# Supply_Driver_12V.net
KiCad netlist of a schematic drawn in Altium Designer
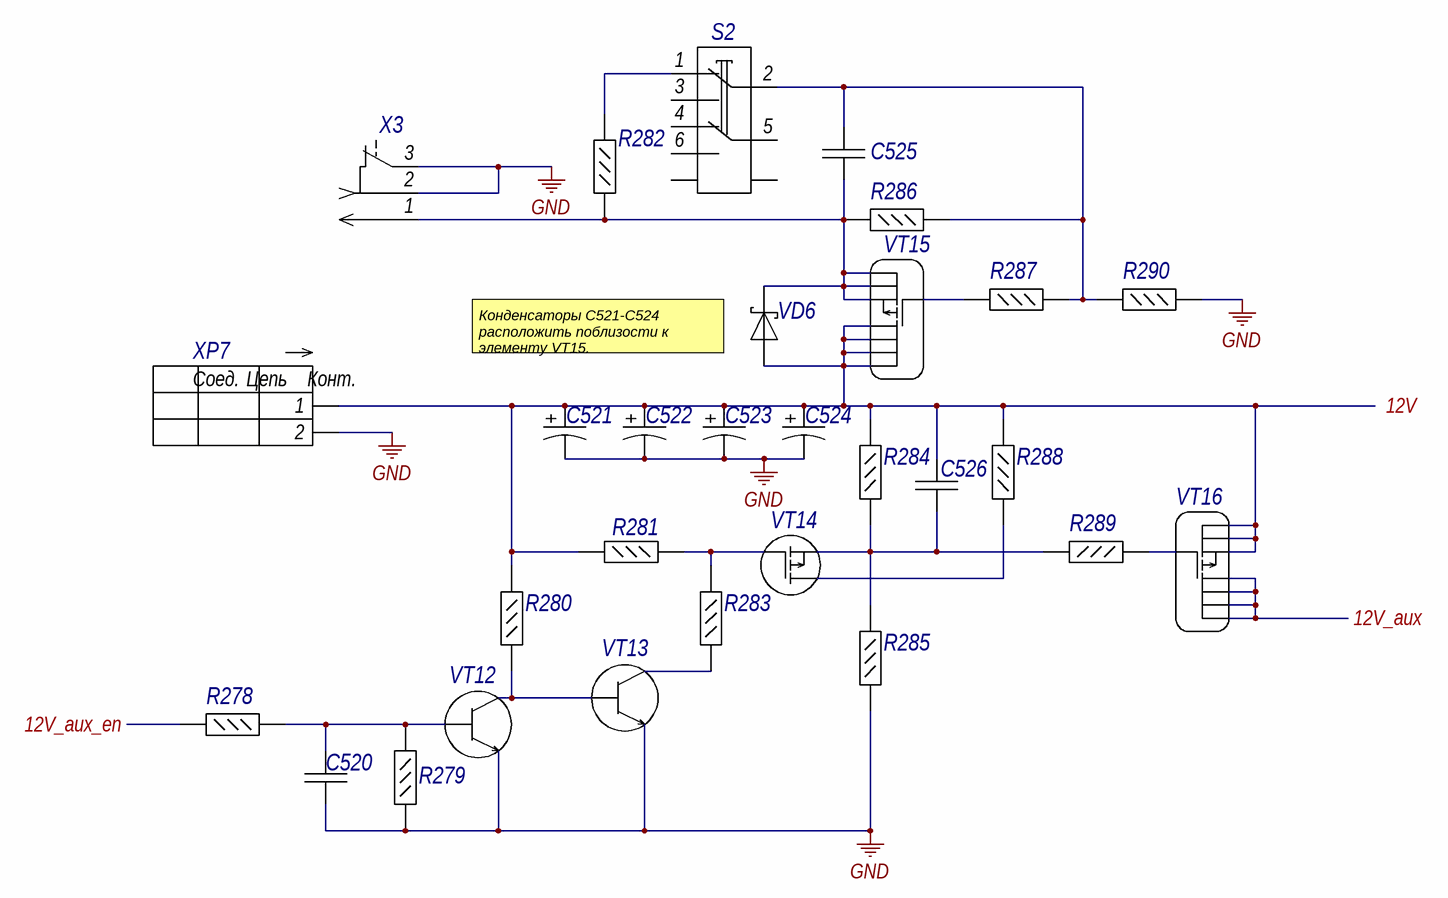
[diagram p0: Supply Driver 12V.SchDoc]

(export (version "E")
  (design (tool "Eeschema 10.0.6"))
  (components
    (comp (ref "C520")
      (value "C1005X7R1E104M")
      (footprint "CAPC1005X55X10LL05")
      (description "Chip Capacitor, 0.1 uF, +/- 20%, 25 V, -55 to 125 degC, 0402 (1005 Metric), RoHS, Tape and Reel")
      (fields (field (name "TOLERANCE") "20%"))
      (libsource (lib "MiniPC DB") (part "CAP_NP"))
    )
    (comp (ref "C521")
      (value "EEH-ZA1E331P")
      (footprint "PNSC-EEH-ZA1E331P_M")
      (fields (field (name "TOLERANCE") "20%"))
      (libsource (lib "MiniPC DB") (part "CAP_P"))
    )
    (comp (ref "C522")
      (value "EEH-ZA1E331P")
      (footprint "PNSC-EEH-ZA1E331P_M")
      (fields (field (name "TOLERANCE") "20%"))
      (libsource (lib "MiniPC DB") (part "CAP_P"))
    )
    (comp (ref "C523")
      (value "EEH-ZA1E331P")
      (footprint "PNSC-EEH-ZA1E331P_M")
      (fields (field (name "TOLERANCE") "20%"))
      (libsource (lib "MiniPC DB") (part "CAP_P"))
    )
    (comp (ref "C524")
      (value "EEH-ZA1E331P")
      (footprint "PNSC-EEH-ZA1E331P_M")
      (fields (field (name "TOLERANCE") "20%"))
      (libsource (lib "MiniPC DB") (part "CAP_P"))
    )
    (comp (ref "C525")
      (value "CGB2A1X5R1E105K033BC")
      (footprint "CAPC1005X33X10LL5")
      (description "Chip Capacitor, 1 uF, +/- 10%, 25 V, -55 to 85 degC, 0402 (1005 Metric), RoHS, Tape and Reel")
      (fields (field (name "TOLERANCE") "10%"))
      (libsource (lib "MiniPC DB") (part "CAP_NP"))
    )
    (comp (ref "C526")
      (value "CGB2A1X5R1E105K033BC")
      (footprint "CAPC1005X33X10LL5")
      (description "Chip Capacitor, 1 uF, +/- 10%, 25 V, -55 to 85 degC, 0402 (1005 Metric), RoHS, Tape and Reel")
      (fields (field (name "TOLERANCE") "10%"))
      (libsource (lib "MiniPC DB") (part "CAP_NP"))
    )
    (comp (ref "R278")
      (value "ERJ-2RKF1001X")
      (footprint "RESC1005X40X25LL05T05")
      (description "Chip Resistor, 1 KOhm, +/- 1%, 100 mW, -55 to 155 degC, 0402 (1005 Metric), RoHS, Tape and Reel")
      (fields (field (name "TOLERANCE") "1%") (field (name "MANUFACTURER") "Basic Passives"))
      (libsource (lib "") (part "RES-0.05_2"))
    )
    (comp (ref "R279")
      (value "ERJ-2RKF1002X")
      (footprint "RESC1005X40X25LL05T05")
      (description "Chip Resistor, 10 KOhm, +/- 1%, 100 mW, -55 to 155 degC, 0402 (1005 Metric), RoHS, Tape and Reel")
      (fields (field (name "TOLERANCE") "1%") (field (name "MANUFACTURER") "Basic Passives"))
      (libsource (lib "MiniPC DB") (part "RES-0.05"))
    )
    (comp (ref "R280")
      (value "ERJ-2RKF4992X")
      (footprint "RESC1005X40X25LL05T05")
      (description "Chip Resistor, 49.9 KOhm, +/- 1%, 100 mW, -55 to 155 degC, 0402 (1005 Metric), RoHS, Tape and Reel")
      (fields (field (name "TOLERANCE") "1%") (field (name "MANUFACTURER") "Basic Passives"))
      (libsource (lib "MiniPC DB") (part "RES-0.05"))
    )
    (comp (ref "R281")
      (value "ERJ-2RKF4992X")
      (footprint "RESC1005X40X25LL05T05")
      (description "Chip Resistor, 49.9 KOhm, +/- 1%, 100 mW, -55 to 155 degC, 0402 (1005 Metric), RoHS, Tape and Reel")
      (fields (field (name "TOLERANCE") "1%") (field (name "MANUFACTURER") "Basic Passives"))
      (libsource (lib "") (part "RES-0.05_1"))
    )
    (comp (ref "R282")
      (value "ERJ-2RKF10R0X")
      (footprint "RESC1005X40X25LL05T05")
      (description "Chip Resistor, 10 Ohm, +/- 1%, 100 mW, -55 to 155 degC, 0402 (1005 Metric), RoHS, Tape and Reel")
      (fields (field (name "TOLERANCE") "1%") (field (name "MANUFACTURER") "Basic Passives"))
      (libsource (lib "") (part "RES-0.05_1"))
    )
    (comp (ref "R283")
      (value "ERJ-2RKF1001X")
      (footprint "RESC1005X40X25LL05T05")
      (description "Chip Resistor, 1 KOhm, +/- 1%, 100 mW, -55 to 155 degC, 0402 (1005 Metric), RoHS, Tape and Reel")
      (fields (field (name "TOLERANCE") "1%") (field (name "MANUFACTURER") "Basic Passives"))
      (libsource (lib "MiniPC DB") (part "RES-0.05"))
    )
    (comp (ref "R284")
      (value "ERJ-2RKF4992X")
      (footprint "RESC1005X40X25LL05T05")
      (description "Chip Resistor, 49.9 KOhm, +/- 1%, 100 mW, -55 to 155 degC, 0402 (1005 Metric), RoHS, Tape and Reel")
      (fields (field (name "TOLERANCE") "1%") (field (name "MANUFACTURER") "Basic Passives"))
      (libsource (lib "MiniPC DB") (part "RES-0.05"))
    )
    (comp (ref "R285")
      (value "ERJ-2RKF1003X")
      (footprint "RESC1005X40X25LL05T05")
      (description "Chip Resistor, 100 KOhm, +/- 1%, 100 mW, -55 to 155 degC, 0402 (1005 Metric), RoHS, Tape and Reel")
      (fields (field (name "TOLERANCE") "1%") (field (name "MANUFACTURER") "Basic Passives"))
      (libsource (lib "MiniPC DB") (part "RES-0.05"))
    )
    (comp (ref "R286")
      (value "ERJ-2RKF4992X")
      (footprint "RESC1005X40X25LL05T05")
      (description "Chip Resistor, 49.9 KOhm, +/- 1%, 100 mW, -55 to 155 degC, 0402 (1005 Metric), RoHS, Tape and Reel")
      (fields (field (name "TOLERANCE") "1%") (field (name "MANUFACTURER") "Basic Passives"))
      (libsource (lib "") (part "RES-0.05_1"))
    )
    (comp (ref "R287")
      (value "ERJ-2RKF10R0X")
      (footprint "RESC1005X40X25LL05T05")
      (description "Chip Resistor, 10 Ohm, +/- 1%, 100 mW, -55 to 155 degC, 0402 (1005 Metric), RoHS, Tape and Reel")
      (fields (field (name "TOLERANCE") "1%") (field (name "MANUFACTURER") "Basic Passives"))
      (libsource (lib "") (part "RES-0.05_1"))
    )
    (comp (ref "R288")
      (value "ERJ-2RKF10R0X")
      (footprint "RESC1005X40X25LL05T05")
      (description "Chip Resistor, 10 Ohm, +/- 1%, 100 mW, -55 to 155 degC, 0402 (1005 Metric), RoHS, Tape and Reel")
      (fields (field (name "TOLERANCE") "1%") (field (name "MANUFACTURER") "Basic Passives"))
      (libsource (lib "") (part "RES-0.05_2"))
    )
    (comp (ref "R289")
      (value "ERJ-2RKF10R0X")
      (footprint "RESC1005X40X25LL05T05")
      (description "Chip Resistor, 10 Ohm, +/- 1%, 100 mW, -55 to 155 degC, 0402 (1005 Metric), RoHS, Tape and Reel")
      (fields (field (name "TOLERANCE") "1%") (field (name "MANUFACTURER") "Basic Passives"))
      (libsource (lib "MiniPC DB") (part "RES-0.05"))
    )
    (comp (ref "R290")
      (value "ERJ-2RKF1003X")
      (footprint "RESC1005X40X25LL05T05")
      (description "Chip Resistor, 100 KOhm, +/- 1%, 100 mW, -55 to 155 degC, 0402 (1005 Metric), RoHS, Tape and Reel")
      (fields (field (name "TOLERANCE") "1%") (field (name "MANUFACTURER") "Basic Passives"))
      (libsource (lib "") (part "RES-0.05_1"))
    )
    (comp (ref "S2")
      (value "EG2207")
      (footprint "ESWI-EG2207_V")
      (description "Slide Switch DPDT, 30 V, -20 to 70 degC, 6-Pin THD, RoHS, Bulk")
      (libsource (lib "MiniPC DB") (part "SW_DPDT_2"))
    )
    (comp (ref "VD6")
      (value "B530C-13-F")
      (footprint "DIOD-SMC-2_V")
      (fields (field (name "MANUFACTURER") "Diodes Inc"))
      (libsource (lib "MiniPC DB") (part "DIODE_SHOTTKI"))
    )
    (comp (ref "VT12")
      (value "MMBT2222A-7-F")
      (footprint "DIOD-SOT23-3_V")
      (description "NPN Small Signal Transistor, 40 V, -55 to 150 degC, 3-Pin SOT23, RoHS, Tape and Reel")
      (fields (field (name "MANUFACTURER") "Diodes Inc"))
      (libsource (lib "MiniPC DB") (part "BJT-NPN-BEC"))
    )
    (comp (ref "VT13")
      (value "MMBT2222A-7-F")
      (footprint "DIOD-SOT23-3_V")
      (description "NPN Small Signal Transistor, 40 V, -55 to 150 degC, 3-Pin SOT23, RoHS, Tape and Reel")
      (fields (field (name "MANUFACTURER") "Diodes Inc"))
      (libsource (lib "") (part "BJT-NPN-BEC_1"))
    )
    (comp (ref "VT14")
      (value "DMP3098L-7")
      (footprint "DIOD-SOT23-3_V")
      (description "P-Channel Enhancement Mode MOSFET, -30 V VDS, -55 to 155 degC, 3-Pin SOT23, RoHS, Tape and Reel")
      (fields (field (name "MANUFACTURER") "Diodes Inc"))
      (libsource (lib "MiniPC DB") (part "MOSFET-P-IND"))
    )
    (comp (ref "VT15")
      (value "Si7635DP-T1-GE3")
      (footprint "VISH-PPAKSO-8_V")
      (description "P-Channel MOSFET, 20 V, -55 to 150 degC, 8-Pin SMD (PPAKSO-8), RoHS, Tape and Reel")
      (libsource (lib "MiniPC DB") (part "MOSFET-P-IND_2"))
    )
    (comp (ref "VT16")
      (value "Si7635DP-T1-GE3")
      (footprint "VISH-PPAKSO-8_V")
      (description "P-Channel MOSFET, 20 V, -55 to 150 degC, 8-Pin SMD (PPAKSO-8), RoHS, Tape and Reel")
      (libsource (lib "MiniPC DB") (part "MOSFET-P-IND_2"))
    )
    (comp (ref "X3")
      (value "16PJ032")
      (footprint "KOBI-16PJ032_V")
      (description "DC Power Jack, Female, -10 to 70 degC, 3-Pin THD, RoHS")
      (libsource (lib "MiniPC DB") (part "PWR_SOED"))
    )
    (comp (ref "XP7")
      (value "613 002 111 21")
      (footprint "WE-61300211121_V")
      (fields (field (name "MANUFACTURER") "Wuerth Elektronik"))
      (libsource (lib "MiniPC DB") (part "VILKA_2K"))
    )
  )
  (nets
    (net (code "1") (name "/12V") (class "Default")
      (node (ref "C521") (pin "1") (pinfunction "1_1") (pintype "passive"))
      (node (ref "C522") (pin "1") (pinfunction "1_1") (pintype "passive"))
      (node (ref "C523") (pin "1") (pinfunction "1_1") (pintype "passive"))
      (node (ref "C524") (pin "1") (pinfunction "1_1") (pintype "passive"))
      (node (ref "C526") (pin "2") (pinfunction "2_2") (pintype "passive"))
      (node (ref "R280") (pin "2") (pinfunction "2_2") (pintype "passive"))
      (node (ref "R281") (pin "2") (pinfunction "2_2") (pintype "passive"))
      (node (ref "R284") (pin "2") (pinfunction "2_2") (pintype "passive"))
      (node (ref "R288") (pin "2") (pinfunction "2_2") (pintype "passive"))
      (node (ref "VD6") (pin "1") (pinfunction "A_1") (pintype "passive"))
      (node (ref "VT15") (pin "5") (pinfunction "D_5") (pintype "passive"))
      (node (ref "VT15") (pin "6") (pinfunction "D_6") (pintype "passive"))
      (node (ref "VT15") (pin "7") (pinfunction "D_7") (pintype "passive"))
      (node (ref "VT15") (pin "8") (pinfunction "D_8") (pintype "passive"))
      (node (ref "VT16") (pin "1") (pinfunction "S_1") (pintype "passive"))
      (node (ref "VT16") (pin "2") (pinfunction "S_2") (pintype "passive"))
      (node (ref "VT16") (pin "3") (pinfunction "S_3") (pintype "passive"))
      (node (ref "XP7") (pin "1") (pinfunction "1_1") (pintype "passive"))
    )
    (net (code "2") (name "/12V_aux") (class "Default")
      (node (ref "VT16") (pin "5") (pinfunction "D_5") (pintype "passive"))
      (node (ref "VT16") (pin "6") (pinfunction "D_6") (pintype "passive"))
      (node (ref "VT16") (pin "7") (pinfunction "D_7") (pintype "passive"))
      (node (ref "VT16") (pin "8") (pinfunction "D_8") (pintype "passive"))
    )
    (net (code "3") (name "/12V_aux_en") (class "Default")
      (node (ref "R278") (pin "1") (pinfunction "1_1") (pintype "passive"))
    )
    (net (code "4") (name "GND") (class "Default")
      (node (ref "C520") (pin "1") (pinfunction "1_1") (pintype "passive"))
      (node (ref "C521") (pin "2") (pinfunction "2_2") (pintype "passive"))
      (node (ref "C522") (pin "2") (pinfunction "2_2") (pintype "passive"))
      (node (ref "C523") (pin "2") (pinfunction "2_2") (pintype "passive"))
      (node (ref "C524") (pin "2") (pinfunction "2_2") (pintype "passive"))
      (node (ref "R279") (pin "1") (pinfunction "1_1") (pintype "passive"))
      (node (ref "R285") (pin "1") (pinfunction "1_1") (pintype "passive"))
      (node (ref "R290") (pin "1") (pinfunction "1_1") (pintype "passive"))
      (node (ref "VT12") (pin "2") (pinfunction "2_2") (pintype "passive"))
      (node (ref "VT13") (pin "2") (pinfunction "2_2") (pintype "passive"))
      (node (ref "X3") (pin "2") (pintype "power_in"))
      (node (ref "X3") (pin "3") (pintype "power_in"))
      (node (ref "XP7") (pin "2") (pinfunction "2_2") (pintype "passive"))
    )
    (net (code "5") (name "Net-(C520-Pad2)") (class "Default")
      (node (ref "C520") (pin "2") (pinfunction "2_2") (pintype "passive"))
      (node (ref "R278") (pin "2") (pinfunction "2_2") (pintype "passive"))
      (node (ref "R279") (pin "2") (pinfunction "2_2") (pintype "passive"))
      (node (ref "VT12") (pin "1") (pinfunction "1_1") (pintype "passive"))
    )
    (net (code "6") (name "Net-(C525-Pad1)") (class "Default")
      (node (ref "C525") (pin "1") (pinfunction "1_1") (pintype "passive"))
      (node (ref "R286") (pin "1") (pinfunction "1_1") (pintype "passive"))
      (node (ref "R287") (pin "1") (pinfunction "1_1") (pintype "passive"))
      (node (ref "R290") (pin "2") (pinfunction "2_2") (pintype "passive"))
      (node (ref "S2") (pin "2") (pinfunction "2_2") (pintype "passive"))
    )
    (net (code "7") (name "Net-(C526-Pad1)") (class "Default")
      (node (ref "C526") (pin "1") (pinfunction "1_1") (pintype "passive"))
      (node (ref "R284") (pin "1") (pinfunction "1_1") (pintype "passive"))
      (node (ref "R285") (pin "2") (pinfunction "2_2") (pintype "passive"))
      (node (ref "R289") (pin "1") (pinfunction "1_1") (pintype "passive"))
      (node (ref "VT14") (pin "2") (pinfunction "2_2") (pintype "passive"))
    )
    (net (code "8") (name "Net-(R280-Pad1)") (class "Default")
      (node (ref "R280") (pin "1") (pinfunction "1_1") (pintype "passive"))
      (node (ref "VT12") (pin "3") (pinfunction "3_3") (pintype "passive"))
      (node (ref "VT13") (pin "1") (pinfunction "1_1") (pintype "passive"))
    )
    (net (code "9") (name "Net-(R281-Pad1)") (class "Default")
      (node (ref "R281") (pin "1") (pinfunction "1_1") (pintype "passive"))
      (node (ref "R283") (pin "2") (pinfunction "2_2") (pintype "passive"))
      (node (ref "VT14") (pin "1") (pinfunction "1_1") (pintype "passive"))
    )
    (net (code "10") (name "Net-(R282-Pad1)") (class "Default")
      (node (ref "R282") (pin "1") (pinfunction "1_1") (pintype "passive"))
      (node (ref "S2") (pin "1") (pinfunction "1_1") (pintype "passive"))
    )
    (net (code "11") (name "Net-(R283-Pad1)") (class "Default")
      (node (ref "R283") (pin "1") (pinfunction "1_1") (pintype "passive"))
      (node (ref "VT13") (pin "3") (pinfunction "3_3") (pintype "passive"))
    )
    (net (code "12") (name "Net-(R288-Pad1)") (class "Default")
      (node (ref "R288") (pin "1") (pinfunction "1_1") (pintype "passive"))
      (node (ref "VT14") (pin "3") (pinfunction "3_3") (pintype "passive"))
    )
    (net (code "13") (name "Net-(VD6-K)") (class "Default")
      (node (ref "C525") (pin "2") (pinfunction "2_2") (pintype "passive"))
      (node (ref "R282") (pin "2") (pinfunction "2_2") (pintype "passive"))
      (node (ref "R286") (pin "2") (pinfunction "2_2") (pintype "passive"))
      (node (ref "VD6") (pin "2") (pinfunction "K_2") (pintype "passive"))
      (node (ref "VT15") (pin "1") (pinfunction "S_1") (pintype "passive"))
      (node (ref "VT15") (pin "2") (pinfunction "S_2") (pintype "passive"))
      (node (ref "VT15") (pin "3") (pinfunction "S_3") (pintype "passive"))
      (node (ref "X3") (pin "1") (pintype "power_in"))
    )
    (net (code "14") (name "Net-(VT15-G)") (class "Default")
      (node (ref "R287") (pin "2") (pinfunction "2_2") (pintype "passive"))
      (node (ref "VT15") (pin "4") (pinfunction "G_4") (pintype "passive"))
    )
    (net (code "15") (name "Net-(VT16-G)") (class "Default")
      (node (ref "R289") (pin "2") (pinfunction "2_2") (pintype "passive"))
      (node (ref "VT16") (pin "4") (pinfunction "G_4") (pintype "passive"))
    )
    (net (code "16") (name "unconnected-(S2-Pad3)") (class "Default")
      (node (ref "S2") (pin "3") (pinfunction "3_3") (pintype "passive"))
    )
    (net (code "17") (name "unconnected-(S2-Pad4)") (class "Default")
      (node (ref "S2") (pin "4") (pinfunction "4_4") (pintype "passive"))
    )
    (net (code "18") (name "unconnected-(S2-Pad5)") (class "Default")
      (node (ref "S2") (pin "5") (pinfunction "5_5") (pintype "passive"))
    )
    (net (code "19") (name "unconnected-(S2-Pad6)") (class "Default")
      (node (ref "S2") (pin "6") (pinfunction "6_6") (pintype "passive"))
    )
    (net (code "20") (name "unconnected-(S2-PadMH1)") (class "Default")
      (node (ref "S2") (pin "MH1") (pinfunction "MH1_MH1") (pintype "passive"))
    )
    (net (code "21") (name "unconnected-(S2-PadMH2)") (class "Default")
      (node (ref "S2") (pin "MH2") (pinfunction "MH2_MH2") (pintype "passive"))
    )
  )
)
